# ESP32_RelayBoard.net
KiCad netlist of a schematic drawn in EasyEDA Pro
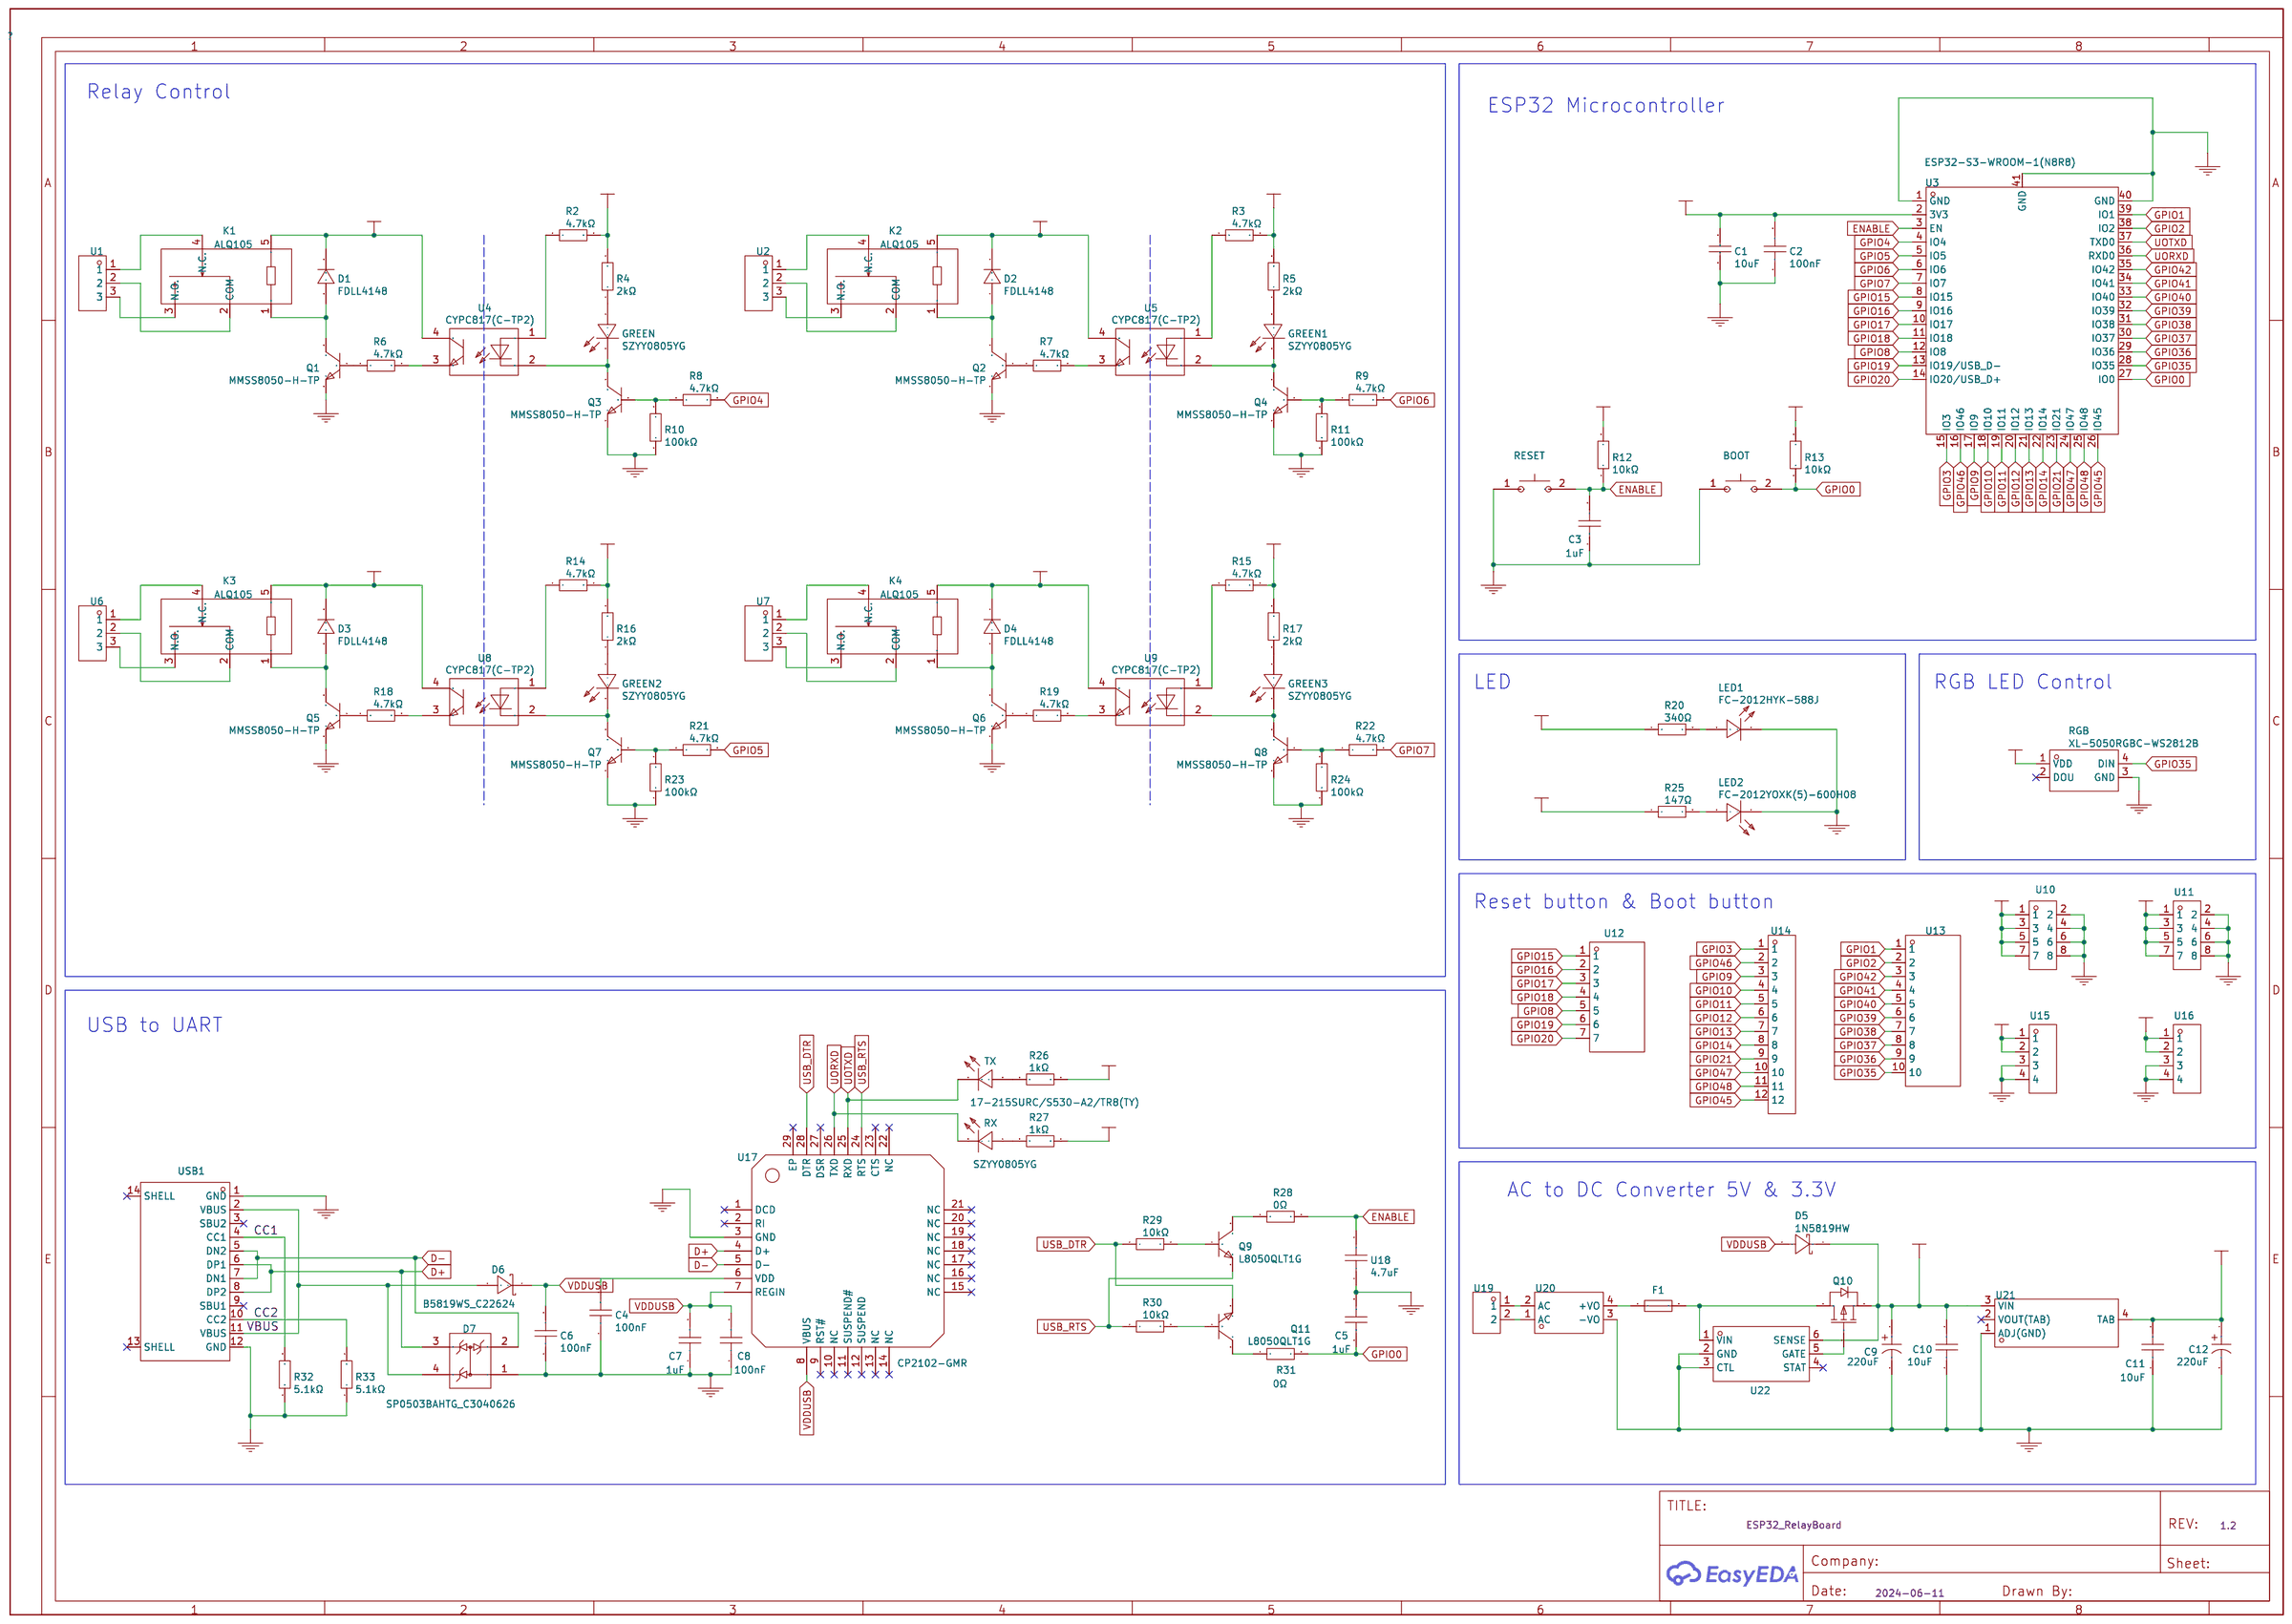
[diagram p0: schematic sheet]

(export (version "E")
  (design (tool "Eeschema 10.0.6"))
  (components
    (comp (ref "BOOT")
      (value "TS-1101S-C-B-B-B-A")
      (footprint "easyedapro:SW-SMD_L6.0-W3.5-LS8.0")
      (fields (field (name "Manufacturer") "XKB Connectivity(中国星坤)"))
      (libsource (lib "easyedapro") (part "TS-1101S-C-B-B-B-A"))
    )
    (comp (ref "C1")
      (value "10uF")
      (footprint "easyedapro:C0402")
      (fields
        (field (name "Manufacturer Part") "CC0402MRX5R5BB106")
        (field (name "Manufacturer") "YAGEO(国巨)")
      )
      (libsource (lib "") (part "10uF_1"))
    )
    (comp (ref "C2")
      (value "100nF")
      (footprint "easyedapro:C0402")
      (fields
        (field (name "Manufacturer Part") "CSA0402X7R104K250GT")
        (field (name "Manufacturer") "HRE(芯声)")
      )
      (libsource (lib "easyedapro") (part "100nF"))
    )
    (comp (ref "C3")
      (value "1uF")
      (footprint "easyedapro:C0402")
      (fields
        (field (name "Manufacturer Part") "HGC0402R5105K500NTEJ")
        (field (name "Manufacturer") "Chinocera(华瓷)")
      )
      (libsource (lib "easyedapro") (part "1uF"))
    )
    (comp (ref "C4")
      (value "100nF")
      (footprint "easyedapro:C0402")
      (fields
        (field (name "Manufacturer Part") "CSA0402X7R104K250GT")
        (field (name "Manufacturer") "HRE(芯声)")
      )
      (libsource (lib "easyedapro") (part "100nF"))
    )
    (comp (ref "C5")
      (value "1uF")
      (footprint "easyedapro:C0402")
      (fields
        (field (name "Manufacturer Part") "HGC0402R5105K500NTEJ")
        (field (name "Manufacturer") "Chinocera(华瓷)")
      )
      (libsource (lib "easyedapro") (part "1uF"))
    )
    (comp (ref "C6")
      (value "100nF")
      (footprint "easyedapro:C0402")
      (fields
        (field (name "Manufacturer Part") "CSA0402X7R104K250GT")
        (field (name "Manufacturer") "HRE(芯声)")
      )
      (libsource (lib "easyedapro") (part "100nF"))
    )
    (comp (ref "C7")
      (value "1uF")
      (footprint "easyedapro:C0402")
      (fields
        (field (name "Manufacturer Part") "HGC0402R5105K500NTEJ")
        (field (name "Manufacturer") "Chinocera(华瓷)")
      )
      (libsource (lib "easyedapro") (part "1uF"))
    )
    (comp (ref "C8")
      (value "100nF")
      (footprint "easyedapro:C0402")
      (fields
        (field (name "Manufacturer Part") "CSA0402X7R104K250GT")
        (field (name "Manufacturer") "HRE(芯声)")
      )
      (libsource (lib "easyedapro") (part "100nF"))
    )
    (comp (ref "C9")
      (value "220uF")
      (footprint "easyedapro:CAP-SMD_BD6.3-L6.6-W6.6-LS7.2-FD")
      (fields
        (field (name "Manufacturer Part") "MVG 16V 220UF 6.3*7.7")
        (field (name "Manufacturer") "SAMYOUNG(韩国三莹)")
      )
      (libsource (lib "easyedapro") (part "220uF"))
    )
    (comp (ref "C10")
      (value "10uF")
      (footprint "easyedapro:C0805")
      (fields (field (name "Manufacturer Part") "0805F106M160NT") (field (name "Manufacturer") "FH(风华)"))
      (libsource (lib "easyedapro") (part "10uF"))
    )
    (comp (ref "C11")
      (value "10uF")
      (footprint "easyedapro:C0805")
      (fields (field (name "Manufacturer Part") "0805F106M160NT") (field (name "Manufacturer") "FH(风华)"))
      (libsource (lib "easyedapro") (part "10uF"))
    )
    (comp (ref "C12")
      (value "220uF")
      (footprint "easyedapro:CAP-SMD_BD6.3-L6.6-W6.6-LS7.2-FD")
      (fields
        (field (name "Manufacturer Part") "MVG 16V 220UF 6.3*7.7")
        (field (name "Manufacturer") "SAMYOUNG(韩国三莹)")
      )
      (libsource (lib "easyedapro") (part "220uF"))
    )
    (comp (ref "D1")
      (value "FDLL4148")
      (footprint "easyedapro:SOD-80_L3.5-W1.5-RD")
      (fields (field (name "Manufacturer") "onsemi(安森美)"))
      (libsource (lib "easyedapro") (part "FDLL4148"))
    )
    (comp (ref "D2")
      (value "FDLL4148")
      (footprint "easyedapro:SOD-80_L3.5-W1.5-RD")
      (fields (field (name "Manufacturer") "onsemi(安森美)"))
      (libsource (lib "easyedapro") (part "FDLL4148"))
    )
    (comp (ref "D3")
      (value "FDLL4148")
      (footprint "easyedapro:SOD-80_L3.5-W1.5-RD")
      (fields (field (name "Manufacturer") "onsemi(安森美)"))
      (libsource (lib "easyedapro") (part "FDLL4148"))
    )
    (comp (ref "D4")
      (value "FDLL4148")
      (footprint "easyedapro:SOD-80_L3.5-W1.5-RD")
      (fields (field (name "Manufacturer") "onsemi(安森美)"))
      (libsource (lib "easyedapro") (part "FDLL4148"))
    )
    (comp (ref "D5")
      (value "1N5819HW")
      (footprint "easyedapro:SOD-123_L2.7-W1.6-LS3.7-RD-1")
      (fields (field (name "Manufacturer") "TECH PUBLIC(台舟)"))
      (libsource (lib "easyedapro") (part "1N5819HW"))
    )
    (comp (ref "D6")
      (value "B5819WS_C22624")
      (footprint "easyedapro:SOD-323_L1.8-W1.3-LS2.5-RD")
      (fields (field (name "Manufacturer Part") "B5819WS") (field (name "Manufacturer") "CJ(江苏长电/长晶)"))
      (libsource (lib "easyedapro") (part "B5819WS_C22624"))
    )
    (comp (ref "D7")
      (value "SP0503BAHTG_C3040626")
      (footprint "easyedapro:SOT-143-4_L2.9-W1.3-P1.92-LS2.4-BL")
      (fields
        (field (name "Manufacturer Part") "SP0503BAHTG")
        (field (name "Manufacturer") "TECH PUBLIC(台舟)")
      )
      (libsource (lib "easyedapro") (part "SP0503BAHTG_C3040626"))
    )
    (comp (ref "F1")
      (value "BSMD0805-100-6V")
      (footprint "easyedapro:F0805")
      (fields (field (name "Manufacturer") "BHFUSE(佰宏)"))
      (libsource (lib "easyedapro") (part "BSMD0805-100-6V"))
    )
    (comp (ref "GREEN")
      (value "SZYY0805YG")
      (footprint "easyedapro:LED0805-R-RD_GREEN")
      (fields (field (name "Manufacturer") "yongyu(永裕光电)"))
      (libsource (lib "easyedapro") (part "SZYY0805YG"))
    )
    (comp (ref "GREEN1")
      (value "SZYY0805YG")
      (footprint "easyedapro:LED0805-R-RD_GREEN")
      (fields (field (name "Manufacturer") "yongyu(永裕光电)"))
      (libsource (lib "easyedapro") (part "SZYY0805YG"))
    )
    (comp (ref "GREEN2")
      (value "SZYY0805YG")
      (footprint "easyedapro:LED0805-R-RD_GREEN")
      (fields (field (name "Manufacturer") "yongyu(永裕光电)"))
      (libsource (lib "easyedapro") (part "SZYY0805YG"))
    )
    (comp (ref "GREEN3")
      (value "SZYY0805YG")
      (footprint "easyedapro:LED0805-R-RD_GREEN")
      (fields (field (name "Manufacturer") "yongyu(永裕光电)"))
      (libsource (lib "easyedapro") (part "SZYY0805YG"))
    )
    (comp (ref "K1")
      (value "ALQ105")
      (footprint "easyedapro:RELAY-TH_ALQ1XX")
      (fields (field (name "Manufacturer") "PANASONIC(松下)"))
      (libsource (lib "easyedapro") (part "ALQ105"))
    )
    (comp (ref "K2")
      (value "ALQ105")
      (footprint "easyedapro:RELAY-TH_ALQ1XX")
      (fields (field (name "Manufacturer") "PANASONIC(松下)"))
      (libsource (lib "easyedapro") (part "ALQ105"))
    )
    (comp (ref "K3")
      (value "ALQ105")
      (footprint "easyedapro:RELAY-TH_ALQ1XX")
      (fields (field (name "Manufacturer") "PANASONIC(松下)"))
      (libsource (lib "easyedapro") (part "ALQ105"))
    )
    (comp (ref "K4")
      (value "ALQ105")
      (footprint "easyedapro:RELAY-TH_ALQ1XX")
      (fields (field (name "Manufacturer") "PANASONIC(松下)"))
      (libsource (lib "easyedapro") (part "ALQ105"))
    )
    (comp (ref "LED1")
      (value "FC-2012HYK-588J")
      (footprint "easyedapro:LED0805-R-RD")
      (fields (field (name "Manufacturer Part") "NCD0805Y1") (field (name "Manufacturer") "国星光电"))
      (libsource (lib "easyedapro") (part "FC-2012HYK-588J"))
    )
    (comp (ref "LED2")
      (value "FC-2012YOXK(5)-600H08")
      (footprint "easyedapro:LED0805-RD_ORANGE")
      (fields (field (name "Manufacturer Part") "NCD0805O1") (field (name "Manufacturer") "国星光电"))
      (libsource (lib "easyedapro") (part "FC-2012YOXK(5)-600H08"))
    )
    (comp (ref "Q1")
      (value "MMSS8050-H-TP")
      (footprint "easyedapro:SOT-23-3_L2.9-W1.6-P1.90-LS2.8-BR")
      (fields (field (name "Manufacturer") "MCC(美微科)"))
      (libsource (lib "easyedapro") (part "MMSS8050-H-TP"))
    )
    (comp (ref "Q2")
      (value "MMSS8050-H-TP")
      (footprint "easyedapro:SOT-23-3_L2.9-W1.6-P1.90-LS2.8-BR")
      (fields (field (name "Manufacturer") "MCC(美微科)"))
      (libsource (lib "easyedapro") (part "MMSS8050-H-TP"))
    )
    (comp (ref "Q3")
      (value "MMSS8050-H-TP")
      (footprint "easyedapro:SOT-23-3_L2.9-W1.6-P1.90-LS2.8-BR")
      (fields (field (name "Manufacturer") "MCC(美微科)"))
      (libsource (lib "easyedapro") (part "MMSS8050-H-TP"))
    )
    (comp (ref "Q4")
      (value "MMSS8050-H-TP")
      (footprint "easyedapro:SOT-23-3_L2.9-W1.6-P1.90-LS2.8-BR")
      (fields (field (name "Manufacturer") "MCC(美微科)"))
      (libsource (lib "easyedapro") (part "MMSS8050-H-TP"))
    )
    (comp (ref "Q5")
      (value "MMSS8050-H-TP")
      (footprint "easyedapro:SOT-23-3_L2.9-W1.6-P1.90-LS2.8-BR")
      (fields (field (name "Manufacturer") "MCC(美微科)"))
      (libsource (lib "easyedapro") (part "MMSS8050-H-TP"))
    )
    (comp (ref "Q6")
      (value "MMSS8050-H-TP")
      (footprint "easyedapro:SOT-23-3_L2.9-W1.6-P1.90-LS2.8-BR")
      (fields (field (name "Manufacturer") "MCC(美微科)"))
      (libsource (lib "easyedapro") (part "MMSS8050-H-TP"))
    )
    (comp (ref "Q7")
      (value "MMSS8050-H-TP")
      (footprint "easyedapro:SOT-23-3_L2.9-W1.6-P1.90-LS2.8-BR")
      (fields (field (name "Manufacturer") "MCC(美微科)"))
      (libsource (lib "easyedapro") (part "MMSS8050-H-TP"))
    )
    (comp (ref "Q8")
      (value "MMSS8050-H-TP")
      (footprint "easyedapro:SOT-23-3_L2.9-W1.6-P1.90-LS2.8-BR")
      (fields (field (name "Manufacturer") "MCC(美微科)"))
      (libsource (lib "easyedapro") (part "MMSS8050-H-TP"))
    )
    (comp (ref "Q9")
      (value "L8050QLT1G")
      (footprint "easyedapro:SOT-23-3_L2.9-W1.3-P1.90-LS2.4-BR")
      (fields (field (name "Manufacturer") "LRC(乐山无线电)"))
      (libsource (lib "") (part "L8050QLT1G_1"))
    )
    (comp (ref "Q10")
      (value "FDN306P")
      (footprint "easyedapro:SOT-23-3_L3.0-W1.7-P0.95-LS2.9-BR")
      (fields (field (name "Manufacturer") "onsemi(安森美)"))
      (libsource (lib "easyedapro") (part "FDN306P"))
    )
    (comp (ref "Q11")
      (value "L8050QLT1G")
      (footprint "easyedapro:SOT-23-3_L2.9-W1.3-P1.90-LS2.4-BR")
      (fields (field (name "Manufacturer") "LRC(乐山无线电)"))
      (libsource (lib "easyedapro") (part "L8050QLT1G"))
    )
    (comp (ref "R2")
      (value "4.7kΩ")
      (footprint "easyedapro:R0805")
      (fields
        (field (name "Manufacturer Part") "0805W8F4701T5E")
        (field (name "Manufacturer") "UNI-ROYAL(厚声)")
      )
      (libsource (lib "easyedapro") (part "4.7kΩ"))
    )
    (comp (ref "R3")
      (value "4.7kΩ")
      (footprint "easyedapro:R0805")
      (fields
        (field (name "Manufacturer Part") "0805W8F4701T5E")
        (field (name "Manufacturer") "UNI-ROYAL(厚声)")
      )
      (libsource (lib "easyedapro") (part "4.7kΩ"))
    )
    (comp (ref "R4")
      (value "2kΩ")
      (footprint "easyedapro:R0805")
      (fields
        (field (name "Manufacturer Part") "0805W8F2001T5E")
        (field (name "Manufacturer") "UNI-ROYAL(厚声)")
      )
      (libsource (lib "easyedapro") (part "2kΩ"))
    )
    (comp (ref "R5")
      (value "2kΩ")
      (footprint "easyedapro:R0805")
      (fields
        (field (name "Manufacturer Part") "0805W8F2001T5E")
        (field (name "Manufacturer") "UNI-ROYAL(厚声)")
      )
      (libsource (lib "easyedapro") (part "2kΩ"))
    )
    (comp (ref "R6")
      (value "4.7kΩ")
      (footprint "easyedapro:R0805")
      (fields
        (field (name "Manufacturer Part") "0805W8F4701T5E")
        (field (name "Manufacturer") "UNI-ROYAL(厚声)")
      )
      (libsource (lib "easyedapro") (part "4.7kΩ"))
    )
    (comp (ref "R7")
      (value "4.7kΩ")
      (footprint "easyedapro:R0805")
      (fields
        (field (name "Manufacturer Part") "0805W8F4701T5E")
        (field (name "Manufacturer") "UNI-ROYAL(厚声)")
      )
      (libsource (lib "easyedapro") (part "4.7kΩ"))
    )
    (comp (ref "R8")
      (value "4.7kΩ")
      (footprint "easyedapro:R0805")
      (fields
        (field (name "Manufacturer Part") "0805W8F4701T5E")
        (field (name "Manufacturer") "UNI-ROYAL(厚声)")
      )
      (libsource (lib "easyedapro") (part "4.7kΩ"))
    )
    (comp (ref "R9")
      (value "4.7kΩ")
      (footprint "easyedapro:R0805")
      (fields
        (field (name "Manufacturer Part") "0805W8F4701T5E")
        (field (name "Manufacturer") "UNI-ROYAL(厚声)")
      )
      (libsource (lib "easyedapro") (part "4.7kΩ"))
    )
    (comp (ref "R10")
      (value "100kΩ")
      (footprint "easyedapro:R0805")
      (fields
        (field (name "Manufacturer Part") "0805W8F1003T5E")
        (field (name "Manufacturer") "UNI-ROYAL(厚声)")
      )
      (libsource (lib "easyedapro") (part "100kΩ"))
    )
    (comp (ref "R11")
      (value "100kΩ")
      (footprint "easyedapro:R0805")
      (fields
        (field (name "Manufacturer Part") "0805W8F1003T5E")
        (field (name "Manufacturer") "UNI-ROYAL(厚声)")
      )
      (libsource (lib "easyedapro") (part "100kΩ"))
    )
    (comp (ref "R12")
      (value "10kΩ")
      (footprint "easyedapro:R0402")
      (fields (field (name "Manufacturer Part") "RT0402DRE0710KL") (field (name "Manufacturer") "YAGEO(国巨)"))
      (libsource (lib "easyedapro") (part "10kΩ"))
    )
    (comp (ref "R13")
      (value "10kΩ")
      (footprint "easyedapro:R0402")
      (fields (field (name "Manufacturer Part") "RT0402DRE0710KL") (field (name "Manufacturer") "YAGEO(国巨)"))
      (libsource (lib "easyedapro") (part "10kΩ"))
    )
    (comp (ref "R14")
      (value "4.7kΩ")
      (footprint "easyedapro:R0805")
      (fields
        (field (name "Manufacturer Part") "0805W8F4701T5E")
        (field (name "Manufacturer") "UNI-ROYAL(厚声)")
      )
      (libsource (lib "easyedapro") (part "4.7kΩ"))
    )
    (comp (ref "R15")
      (value "4.7kΩ")
      (footprint "easyedapro:R0805")
      (fields
        (field (name "Manufacturer Part") "0805W8F4701T5E")
        (field (name "Manufacturer") "UNI-ROYAL(厚声)")
      )
      (libsource (lib "easyedapro") (part "4.7kΩ"))
    )
    (comp (ref "R16")
      (value "2kΩ")
      (footprint "easyedapro:R0805")
      (fields
        (field (name "Manufacturer Part") "0805W8F2001T5E")
        (field (name "Manufacturer") "UNI-ROYAL(厚声)")
      )
      (libsource (lib "easyedapro") (part "2kΩ"))
    )
    (comp (ref "R17")
      (value "2kΩ")
      (footprint "easyedapro:R0805")
      (fields
        (field (name "Manufacturer Part") "0805W8F2001T5E")
        (field (name "Manufacturer") "UNI-ROYAL(厚声)")
      )
      (libsource (lib "easyedapro") (part "2kΩ"))
    )
    (comp (ref "R18")
      (value "4.7kΩ")
      (footprint "easyedapro:R0805")
      (fields
        (field (name "Manufacturer Part") "0805W8F4701T5E")
        (field (name "Manufacturer") "UNI-ROYAL(厚声)")
      )
      (libsource (lib "easyedapro") (part "4.7kΩ"))
    )
    (comp (ref "R19")
      (value "4.7kΩ")
      (footprint "easyedapro:R0805")
      (fields
        (field (name "Manufacturer Part") "0805W8F4701T5E")
        (field (name "Manufacturer") "UNI-ROYAL(厚声)")
      )
      (libsource (lib "easyedapro") (part "4.7kΩ"))
    )
    (comp (ref "R20")
      (value "340Ω")
      (footprint "easyedapro:R0805")
      (fields (field (name "Manufacturer Part") "CR0805F83400G") (field (name "Manufacturer") "LIZ(丽智电子)"))
      (libsource (lib "easyedapro") (part "340Ω"))
    )
    (comp (ref "R21")
      (value "4.7kΩ")
      (footprint "easyedapro:R0805")
      (fields
        (field (name "Manufacturer Part") "0805W8F4701T5E")
        (field (name "Manufacturer") "UNI-ROYAL(厚声)")
      )
      (libsource (lib "easyedapro") (part "4.7kΩ"))
    )
    (comp (ref "R22")
      (value "4.7kΩ")
      (footprint "easyedapro:R0805")
      (fields
        (field (name "Manufacturer Part") "0805W8F4701T5E")
        (field (name "Manufacturer") "UNI-ROYAL(厚声)")
      )
      (libsource (lib "easyedapro") (part "4.7kΩ"))
    )
    (comp (ref "R23")
      (value "100kΩ")
      (footprint "easyedapro:R0805")
      (fields
        (field (name "Manufacturer Part") "0805W8F1003T5E")
        (field (name "Manufacturer") "UNI-ROYAL(厚声)")
      )
      (libsource (lib "easyedapro") (part "100kΩ"))
    )
    (comp (ref "R24")
      (value "100kΩ")
      (footprint "easyedapro:R0805")
      (fields
        (field (name "Manufacturer Part") "0805W8F1003T5E")
        (field (name "Manufacturer") "UNI-ROYAL(厚声)")
      )
      (libsource (lib "easyedapro") (part "100kΩ"))
    )
    (comp (ref "R25")
      (value "147Ω")
      (footprint "easyedapro:R0805")
      (fields (field (name "Manufacturer Part") "CR0805-FX-1470ELF") (field (name "Manufacturer") "BOURNS"))
      (libsource (lib "easyedapro") (part "147Ω"))
    )
    (comp (ref "R26")
      (value "1kΩ")
      (footprint "easyedapro:R0805")
      (fields (field (name "Manufacturer Part") "RMC08051K5%N") (field (name "Manufacturer") "Tyohm(幸亚电阻)"))
      (libsource (lib "easyedapro") (part "1kΩ"))
    )
    (comp (ref "R27")
      (value "1kΩ")
      (footprint "easyedapro:R0805")
      (fields (field (name "Manufacturer Part") "RMC08051K5%N") (field (name "Manufacturer") "Tyohm(幸亚电阻)"))
      (libsource (lib "easyedapro") (part "1kΩ"))
    )
    (comp (ref "R28")
      (value "0Ω")
      (footprint "easyedapro:R0402")
      (fields (field (name "Manufacturer Part") "RC0402FR-070RL") (field (name "Manufacturer") "YAGEO(国巨)"))
      (libsource (lib "easyedapro") (part "0Ω"))
    )
    (comp (ref "R29")
      (value "10kΩ")
      (footprint "easyedapro:R0402")
      (fields (field (name "Manufacturer Part") "RT0402DRE0710KL") (field (name "Manufacturer") "YAGEO(国巨)"))
      (libsource (lib "easyedapro") (part "10kΩ"))
    )
    (comp (ref "R30")
      (value "10kΩ")
      (footprint "easyedapro:R0402")
      (fields (field (name "Manufacturer Part") "RT0402DRE0710KL") (field (name "Manufacturer") "YAGEO(国巨)"))
      (libsource (lib "easyedapro") (part "10kΩ"))
    )
    (comp (ref "R31")
      (value "0Ω")
      (footprint "easyedapro:R0402")
      (fields (field (name "Manufacturer Part") "RC0402FR-070RL") (field (name "Manufacturer") "YAGEO(国巨)"))
      (libsource (lib "easyedapro") (part "0Ω"))
    )
    (comp (ref "R32")
      (value "5.1kΩ")
      (footprint "easyedapro:R0402")
      (fields (field (name "Manufacturer Part") "RMC04025.1K1%N") (field (name "Manufacturer") "Tyohm(幸亚电阻)"))
      (libsource (lib "easyedapro") (part "5.1kΩ"))
    )
    (comp (ref "R33")
      (value "5.1kΩ")
      (footprint "easyedapro:R0402")
      (fields (field (name "Manufacturer Part") "RMC04025.1K1%N") (field (name "Manufacturer") "Tyohm(幸亚电阻)"))
      (libsource (lib "easyedapro") (part "5.1kΩ"))
    )
    (comp (ref "RESET")
      (value "TS-1101S-C-B-B-B-A")
      (footprint "easyedapro:SW-SMD_L6.0-W3.5-LS8.0")
      (fields (field (name "Manufacturer") "XKB Connectivity(中国星坤)"))
      (libsource (lib "easyedapro") (part "TS-1101S-C-B-B-B-A"))
    )
    (comp (ref "RGB")
      (value "XL-5050RGBC-WS2812B")
      (footprint "easyedapro:LED-SMD_4P-L5.0-W5.0-BL_XL-5050RGBC")
      (fields (field (name "Manufacturer") "XINGLIGHT(成兴光)"))
      (libsource (lib "easyedapro") (part "XL-5050RGBC-WS2812B"))
    )
    (comp (ref "RX")
      (value "SZYY0805YG")
      (footprint "easyedapro:LED0805-R-RD_GREEN")
      (fields (field (name "Manufacturer") "yongyu(永裕光电)"))
      (libsource (lib "easyedapro") (part "SZYY0805YG"))
    )
    (comp (ref "TX")
      (value "17-215SURC/S530-A2/TR8(TY)")
      (footprint "easyedapro:LED0805-RD_RED")
      (fields
        (field (name "Manufacturer Part") "17-215SURC/S530-A2/TR8")
        (field (name "Manufacturer") "EVERLIGHT(亿光)")
      )
      (libsource (lib "easyedapro") (part "17-215SURC/S530-A2/TR8(TY)"))
    )
    (comp (ref "U1")
      (value "DB128L-5.08-3P-BK-S")
      (footprint "easyedapro:CONN-TH_3P-P5.08_DB128L-5.08-3P-BK-S")
      (fields (field (name "Manufacturer") "DORABO(地博电气)"))
      (libsource (lib "easyedapro") (part "DB128L-5.08-3P-BK-S"))
    )
    (comp (ref "U2")
      (value "DB128L-5.08-3P-BK-S")
      (footprint "easyedapro:CONN-TH_3P-P5.08_DB128L-5.08-3P-BK-S")
      (fields (field (name "Manufacturer") "DORABO(地博电气)"))
      (libsource (lib "easyedapro") (part "DB128L-5.08-3P-BK-S"))
    )
    (comp (ref "U3")
      (value "ESP32-S3-WROOM-1(N8R8)")
      (footprint "easyedapro:WIRELM-SMD_ESP32-S3-WROOM-1")
      (fields
        (field (name "Manufacturer Part") "ESP32-S3-WROOM-1-N8R8")
        (field (name "Manufacturer") "ESPRESSIF(乐鑫)")
      )
      (libsource (lib "easyedapro") (part "ESP32-S3-WROOM-1(N8R8)"))
    )
    (comp (ref "U4")
      (value "CYPC817(C-TP2)")
      (footprint "easyedapro:SOP-4_L6.4-W4.6-P2.54-LS10.2-TL")
      (fields (field (name "Manufacturer") "OCIC(卓睿科)"))
      (libsource (lib "easyedapro") (part "CYPC817(C-TP2)"))
    )
    (comp (ref "U5")
      (value "CYPC817(C-TP2)")
      (footprint "easyedapro:SOP-4_L6.4-W4.6-P2.54-LS10.2-TL")
      (fields (field (name "Manufacturer") "OCIC(卓睿科)"))
      (libsource (lib "easyedapro") (part "CYPC817(C-TP2)"))
    )
    (comp (ref "U6")
      (value "DB128L-5.08-3P-BK-S")
      (footprint "easyedapro:CONN-TH_3P-P5.08_DB128L-5.08-3P-BK-S")
      (fields (field (name "Manufacturer") "DORABO(地博电气)"))
      (libsource (lib "easyedapro") (part "DB128L-5.08-3P-BK-S"))
    )
    (comp (ref "U7")
      (value "DB128L-5.08-3P-BK-S")
      (footprint "easyedapro:CONN-TH_3P-P5.08_DB128L-5.08-3P-BK-S")
      (fields (field (name "Manufacturer") "DORABO(地博电气)"))
      (libsource (lib "easyedapro") (part "DB128L-5.08-3P-BK-S"))
    )
    (comp (ref "U8")
      (value "CYPC817(C-TP2)")
      (footprint "easyedapro:SOP-4_L6.4-W4.6-P2.54-LS10.2-TL")
      (fields (field (name "Manufacturer") "OCIC(卓睿科)"))
      (libsource (lib "easyedapro") (part "CYPC817(C-TP2)"))
    )
    (comp (ref "U9")
      (value "CYPC817(C-TP2)")
      (footprint "easyedapro:SOP-4_L6.4-W4.6-P2.54-LS10.2-TL")
      (fields (field (name "Manufacturer") "OCIC(卓睿科)"))
      (libsource (lib "easyedapro") (part "CYPC817(C-TP2)"))
    )
    (comp (ref "U10")
      (value "ZX-PM2.54-2-4PY")
      (footprint "easyedapro:HDR-TH_8P-P2.54-V-F-R2-C4-S2.54")
      (fields (field (name "Manufacturer") "Megastar(兆星)"))
      (libsource (lib "easyedapro") (part "ZX-PM2.54-2-4PY"))
    )
    (comp (ref "U11")
      (value "ZX-PM2.54-2-4PY")
      (footprint "easyedapro:HDR-TH_8P-P2.54-V-F-R2-C4-S2.54")
      (fields (field (name "Manufacturer") "Megastar(兆星)"))
      (libsource (lib "easyedapro") (part "ZX-PM2.54-2-4PY"))
    )
    (comp (ref "U12")
      (value "A2541HWV-7P")
      (footprint "easyedapro:HDR-TH_7P-P2.54-V_A2541HWV-7P")
      (fields (field (name "Manufacturer") "CJT(长江连接器)"))
      (libsource (lib "easyedapro") (part "A2541HWV-7P"))
    )
    (comp (ref "U13")
      (value "A2541HWV-10P")
      (footprint "easyedapro:HDR-TH_10P-P2.54-V-F-1")
      (fields (field (name "Manufacturer") "CJT(长江连接器)"))
      (libsource (lib "easyedapro") (part "A2541HWV-10P"))
    )
    (comp (ref "U14")
      (value "ZX-PM2.54-1-12PY")
      (footprint "easyedapro:HDR-TH_12P-P2.54-V-F")
      (fields (field (name "Manufacturer") "Megastar(兆星)"))
      (libsource (lib "easyedapro") (part "ZX-PM2.54-1-12PY"))
    )
    (comp (ref "U15")
      (value "HB-PH3-25414PB2GOP")
      (footprint "easyedapro:HDR-TH_4P-P2.54-V-M")
      (fields (field (name "Manufacturer") "HANBO(汉博)"))
      (libsource (lib "easyedapro") (part "HB-PH3-25414PB2GOP"))
    )
    (comp (ref "U16")
      (value "HB-PH3-25414PB2GOP")
      (footprint "easyedapro:HDR-TH_4P-P2.54-V-M")
      (fields (field (name "Manufacturer") "HANBO(汉博)"))
      (libsource (lib "easyedapro") (part "HB-PH3-25414PB2GOP"))
    )
    (comp (ref "U17")
      (value "CP2102-GMR")
      (footprint "easyedapro:WQFN-28_L5.0-W5.0-P0.50-BL-EP3.2")
      (fields (field (name "Manufacturer") "SKYWORKS/SILICON LABS(芯科)"))
      (libsource (lib "easyedapro") (part "CP2102-GMR"))
    )
    (comp (ref "U18")
      (value "4.7uF")
      (footprint "easyedapro:C0402")
      (fields
        (field (name "Manufacturer Part") "HGC0402R5475K100NTEJ")
        (field (name "Manufacturer") "Chinocera(华瓷)")
      )
      (libsource (lib "easyedapro") (part "4.7uF"))
    )
    (comp (ref "U19")
      (value "DB128L-5.08-2P-BK-S")
      (footprint "easyedapro:CONN-TH_2P-P5.08_DB128L-5.08-2P-BK-S")
      (fields (field (name "Manufacturer") "DORABO(地博电气)"))
      (libsource (lib "easyedapro") (part "DB128L-5.08-2P-BK-S"))
    )
    (comp (ref "U20")
      (value "HLK-10M05")
      (footprint "easyedapro:PWRM-TH_HLK-10M05")
      (fields (field (name "Manufacturer") "HI-LINK(海凌科)"))
      (libsource (lib "easyedapro") (part "HLK-10M05"))
    )
    (comp (ref "U21")
      (value "AMS1117-3.3_C347222")
      (footprint "easyedapro:SOT-223-4_L6.5-W3.5-P2.30-LS7.0-BR")
      (fields (field (name "Manufacturer Part") "AMS1117-3.3") (field (name "Manufacturer") "UMW(友台半导体)"))
      (libsource (lib "easyedapro") (part "AMS1117-3.3_C347222"))
    )
    (comp (ref "U22")
      (value "LTC4412HVIS6#TRPBF")
      (footprint "easyedapro:TSOT-23-6_L2.9-W1.6-P0.95-LS2.8-BR")
      (fields (field (name "Manufacturer") "ADI(亚德诺)"))
      (libsource (lib "easyedapro") (part "LTC4412HVIS6#TRPBF"))
    )
    (comp (ref "USB1")
      (value "TYPE-C 16PIN 2MD(073)")
      (footprint "easyedapro:USB-C-SMD_TYPE-C-6PIN-2MD-073")
      (fields (field (name "Manufacturer") "SHOU HAN(首韩)"))
      (libsource (lib "easyedapro") (part "TYPE-C 16PIN 2MD(073)"))
    )
  )
  (nets
    (net (code "1") (name "+5V") (class "Default")
      (node (ref "C10") (pin "2") (pinfunction "2_2") (pintype "unspecified"))
      (node (ref "C9") (pin "1") (pinfunction "1_1") (pintype "input"))
      (node (ref "D1") (pin "1") (pinfunction "C_1") (pintype "unspecified"))
      (node (ref "D2") (pin "1") (pinfunction "C_1") (pintype "unspecified"))
      (node (ref "D3") (pin "1") (pinfunction "C_1") (pintype "unspecified"))
      (node (ref "D4") (pin "1") (pinfunction "C_1") (pintype "unspecified"))
      (node (ref "D5") (pin "1") (pinfunction "K_1") (pintype "unspecified"))
      (node (ref "K1") (pin "5") (pinfunction "5_5") (pintype "unspecified"))
      (node (ref "K2") (pin "5") (pinfunction "5_5") (pintype "unspecified"))
      (node (ref "K3") (pin "5") (pinfunction "5_5") (pintype "unspecified"))
      (node (ref "K4") (pin "5") (pinfunction "5_5") (pintype "unspecified"))
      (node (ref "Q10") (pin "2") (pinfunction "S_2") (pintype "unspecified"))
      (node (ref "R20") (pin "1") (pinfunction "1_1") (pintype "unspecified"))
      (node (ref "RGB") (pin "1") (pinfunction "VDD_1") (pintype "unspecified"))
      (node (ref "U11") (pin "1") (pinfunction "1_1") (pintype "unspecified"))
      (node (ref "U11") (pin "3") (pinfunction "3_3") (pintype "unspecified"))
      (node (ref "U11") (pin "5") (pinfunction "5_5") (pintype "unspecified"))
      (node (ref "U11") (pin "7") (pinfunction "7_7") (pintype "unspecified"))
      (node (ref "U16") (pin "1") (pinfunction "1_1") (pintype "unspecified"))
      (node (ref "U16") (pin "2") (pinfunction "2_2") (pintype "unspecified"))
      (node (ref "U21") (pin "3") (pinfunction "VIN_3") (pintype "unspecified"))
      (node (ref "U22") (pin "6") (pinfunction "SENSE_6") (pintype "unspecified"))
      (node (ref "U4") (pin "4") (pinfunction "COL_4") (pintype "unspecified"))
      (node (ref "U5") (pin "4") (pinfunction "COL_4") (pintype "unspecified"))
      (node (ref "U8") (pin "4") (pinfunction "COL_4") (pintype "unspecified"))
      (node (ref "U9") (pin "4") (pinfunction "COL_4") (pintype "unspecified"))
    )
    (net (code "2") (name "/CC1") (class "Default")
      (node (ref "R32") (pin "2") (pinfunction "2_2") (pintype "unspecified"))
      (node (ref "USB1") (pin "4") (pinfunction "CC1_4") (pintype "unspecified"))
    )
    (net (code "3") (name "/CC2") (class "Default")
      (node (ref "R33") (pin "2") (pinfunction "2_2") (pintype "unspecified"))
      (node (ref "USB1") (pin "10") (pinfunction "CC2_10") (pintype "unspecified"))
    )
    (net (code "4") (name "/VBUS") (class "Default")
      (node (ref "D6") (pin "2") (pinfunction "A_2") (pintype "unspecified"))
      (node (ref "D7") (pin "4") (pinfunction "4_4") (pintype "input"))
      (node (ref "USB1") (pin "11") (pinfunction "VBUS_11") (pintype "unspecified"))
      (node (ref "USB1") (pin "2") (pinfunction "VBUS_2") (pintype "unspecified"))
    )
    (net (code "5") (name "3V3") (class "Default")
      (node (ref "C1") (pin "2") (pinfunction "2_2") (pintype "input"))
      (node (ref "C11") (pin "2") (pinfunction "2_2") (pintype "unspecified"))
      (node (ref "C12") (pin "1") (pinfunction "1_1") (pintype "input"))
      (node (ref "C2") (pin "2") (pinfunction "2_2") (pintype "unspecified"))
      (node (ref "R12") (pin "2") (pinfunction "2_2") (pintype "unspecified"))
      (node (ref "R13") (pin "2") (pinfunction "2_2") (pintype "unspecified"))
      (node (ref "R14") (pin "2") (pinfunction "2_2") (pintype "input"))
      (node (ref "R15") (pin "2") (pinfunction "2_2") (pintype "input"))
      (node (ref "R16") (pin "2") (pinfunction "2_2") (pintype "input"))
      (node (ref "R17") (pin "2") (pinfunction "2_2") (pintype "input"))
      (node (ref "R2") (pin "2") (pinfunction "2_2") (pintype "input"))
      (node (ref "R25") (pin "1") (pinfunction "1_1") (pintype "unspecified"))
      (node (ref "R26") (pin "1") (pinfunction "1_1") (pintype "unspecified"))
      (node (ref "R27") (pin "1") (pinfunction "1_1") (pintype "unspecified"))
      (node (ref "R3") (pin "2") (pinfunction "2_2") (pintype "input"))
      (node (ref "R4") (pin "2") (pinfunction "2_2") (pintype "input"))
      (node (ref "R5") (pin "2") (pinfunction "2_2") (pintype "input"))
      (node (ref "U10") (pin "1") (pinfunction "1_1") (pintype "unspecified"))
      (node (ref "U10") (pin "3") (pinfunction "3_3") (pintype "unspecified"))
      (node (ref "U10") (pin "5") (pinfunction "5_5") (pintype "unspecified"))
      (node (ref "U10") (pin "7") (pinfunction "7_7") (pintype "unspecified"))
      (node (ref "U15") (pin "1") (pinfunction "1_1") (pintype "unspecified"))
      (node (ref "U15") (pin "2") (pinfunction "2_2") (pintype "unspecified"))
      (node (ref "U21") (pin "4") (pinfunction "TAB_4") (pintype "unspecified"))
      (node (ref "U3") (pin "2") (pinfunction "3V3_2") (pintype "unspecified"))
    )
    (net (code "6") (name "D+") (class "Default")
      (node (ref "D7") (pin "3") (pinfunction "3_3") (pintype "input"))
      (node (ref "U17") (pin "4") (pinfunction "D+_4") (pintype "unspecified"))
      (node (ref "USB1") (pin "6") (pinfunction "DP1_6") (pintype "unspecified"))
      (node (ref "USB1") (pin "8") (pinfunction "DP2_8") (pintype "unspecified"))
    )
    (net (code "7") (name "D-") (class "Default")
      (node (ref "D7") (pin "2") (pinfunction "2_2") (pintype "input"))
      (node (ref "U17") (pin "5") (pinfunction "D-_5") (pintype "unspecified"))
      (node (ref "USB1") (pin "5") (pinfunction "DN2_5") (pintype "unspecified"))
      (node (ref "USB1") (pin "7") (pinfunction "DN1_7") (pintype "unspecified"))
    )
    (net (code "8") (name "ENABLE") (class "Default")
      (node (ref "C3") (pin "2") (pinfunction "2_2") (pintype "unspecified"))
      (node (ref "R12") (pin "1") (pinfunction "1_1") (pintype "unspecified"))
      (node (ref "R28") (pin "2") (pinfunction "2_2") (pintype "input"))
      (node (ref "RESET") (pin "2") (pinfunction "2_2") (pintype "unspecified"))
      (node (ref "U18") (pin "2") (pinfunction "2_2") (pintype "unspecified"))
      (node (ref "U3") (pin "3") (pinfunction "EN_3") (pintype "unspecified"))
    )
    (net (code "9") (name "GND") (class "Default")
      (node (ref "BOOT") (pin "1") (pinfunction "1_1") (pintype "unspecified"))
      (node (ref "C1") (pin "1") (pinfunction "1_1") (pintype "input"))
      (node (ref "C10") (pin "1") (pinfunction "1_1") (pintype "unspecified"))
      (node (ref "C11") (pin "1") (pinfunction "1_1") (pintype "unspecified"))
      (node (ref "C12") (pin "2") (pinfunction "2_2") (pintype "input"))
      (node (ref "C2") (pin "1") (pinfunction "1_1") (pintype "unspecified"))
      (node (ref "C3") (pin "1") (pinfunction "1_1") (pintype "unspecified"))
      (node (ref "C4") (pin "1") (pinfunction "1_1") (pintype "unspecified"))
      (node (ref "C5") (pin "2") (pinfunction "2_2") (pintype "unspecified"))
      (node (ref "C6") (pin "1") (pinfunction "1_1") (pintype "unspecified"))
      (node (ref "C7") (pin "1") (pinfunction "1_1") (pintype "unspecified"))
      (node (ref "C8") (pin "1") (pinfunction "1_1") (pintype "unspecified"))
      (node (ref "C9") (pin "2") (pinfunction "2_2") (pintype "input"))
      (node (ref "D7") (pin "1") (pinfunction "1_1") (pintype "input"))
      (node (ref "LED1") (pin "2") (pinfunction "K_2") (pintype "unspecified"))
      (node (ref "LED2") (pin "1") (pinfunction "-_1") (pintype "unspecified"))
      (node (ref "Q1") (pin "2") (pinfunction "E_2") (pintype "input"))
      (node (ref "Q2") (pin "2") (pinfunction "E_2") (pintype "input"))
      (node (ref "Q3") (pin "2") (pinfunction "E_2") (pintype "input"))
      (node (ref "Q4") (pin "2") (pinfunction "E_2") (pintype "input"))
      (node (ref "Q5") (pin "2") (pinfunction "E_2") (pintype "input"))
      (node (ref "Q6") (pin "2") (pinfunction "E_2") (pintype "input"))
      (node (ref "Q7") (pin "2") (pinfunction "E_2") (pintype "input"))
      (node (ref "Q8") (pin "2") (pinfunction "E_2") (pintype "input"))
      (node (ref "R10") (pin "1") (pinfunction "1_1") (pintype "unspecified"))
      (node (ref "R11") (pin "1") (pinfunction "1_1") (pintype "unspecified"))
      (node (ref "R23") (pin "1") (pinfunction "1_1") (pintype "unspecified"))
      (node (ref "R24") (pin "1") (pinfunction "1_1") (pintype "unspecified"))
      (node (ref "R32") (pin "1") (pinfunction "1_1") (pintype "unspecified"))
      (node (ref "R33") (pin "1") (pinfunction "1_1") (pintype "unspecified"))
      (node (ref "RESET") (pin "1") (pinfunction "1_1") (pintype "unspecified"))
      (node (ref "RGB") (pin "3") (pinfunction "GND_3") (pintype "unspecified"))
      (node (ref "U10") (pin "2") (pinfunction "2_2") (pintype "unspecified"))
      (node (ref "U10") (pin "4") (pinfunction "4_4") (pintype "unspecified"))
      (node (ref "U10") (pin "6") (pinfunction "6_6") (pintype "unspecified"))
      (node (ref "U10") (pin "8") (pinfunction "8_8") (pintype "unspecified"))
      (node (ref "U11") (pin "2") (pinfunction "2_2") (pintype "unspecified"))
      (node (ref "U11") (pin "4") (pinfunction "4_4") (pintype "unspecified"))
      (node (ref "U11") (pin "6") (pinfunction "6_6") (pintype "unspecified"))
      (node (ref "U11") (pin "8") (pinfunction "8_8") (pintype "unspecified"))
      (node (ref "U15") (pin "3") (pinfunction "3_3") (pintype "unspecified"))
      (node (ref "U15") (pin "4") (pinfunction "4_4") (pintype "unspecified"))
      (node (ref "U16") (pin "3") (pinfunction "3_3") (pintype "unspecified"))
      (node (ref "U16") (pin "4") (pinfunction "4_4") (pintype "unspecified"))
      (node (ref "U17") (pin "3") (pinfunction "GND_3") (pintype "unspecified"))
      (node (ref "U18") (pin "1") (pinfunction "1_1") (pintype "unspecified"))
      (node (ref "U20") (pin "3") (pinfunction "-VO_3") (pintype "unspecified"))
      (node (ref "U21") (pin "1") (pinfunction "ADJ(GND)_1") (pintype "unspecified"))
      (node (ref "U22") (pin "2") (pinfunction "GND_2") (pintype "unspecified"))
      (node (ref "U22") (pin "3") (pinfunction "CTL_3") (pintype "unspecified"))
      (node (ref "U3") (pin "1") (pinfunction "GND_1") (pintype "unspecified"))
      (node (ref "U3") (pin "40") (pinfunction "GND_40") (pintype "unspecified"))
      (node (ref "U3") (pin "41") (pinfunction "GND_41") (pintype "unspecified"))
      (node (ref "USB1") (pin "1") (pinfunction "GND_1") (pintype "unspecified"))
      (node (ref "USB1") (pin "12") (pinfunction "GND_12") (pintype "unspecified"))
    )
    (net (code "10") (name "GPIO0") (class "Default")
      (node (ref "BOOT") (pin "2") (pinfunction "2_2") (pintype "unspecified"))
      (node (ref "C5") (pin "1") (pinfunction "1_1") (pintype "unspecified"))
      (node (ref "R13") (pin "1") (pinfunction "1_1") (pintype "unspecified"))
      (node (ref "R31") (pin "2") (pinfunction "2_2") (pintype "input"))
      (node (ref "U3") (pin "27") (pinfunction "IO0_27") (pintype "unspecified"))
    )
    (net (code "11") (name "GPIO1") (class "Default")
      (node (ref "U13") (pin "1") (pinfunction "1_1") (pintype "unspecified"))
      (node (ref "U3") (pin "39") (pinfunction "IO1_39") (pintype "unspecified"))
    )
    (net (code "12") (name "GPIO2") (class "Default")
      (node (ref "U13") (pin "2") (pinfunction "2_2") (pintype "unspecified"))
      (node (ref "U3") (pin "38") (pinfunction "IO2_38") (pintype "unspecified"))
    )
    (net (code "13") (name "GPIO3") (class "Default")
      (node (ref "U14") (pin "1") (pinfunction "1_1") (pintype "unspecified"))
      (node (ref "U3") (pin "15") (pinfunction "IO3_15") (pintype "unspecified"))
    )
    (net (code "14") (name "GPIO4") (class "Default")
      (node (ref "R8") (pin "2") (pinfunction "2_2") (pintype "input"))
      (node (ref "U3") (pin "4") (pinfunction "IO4_4") (pintype "unspecified"))
    )
    (net (code "15") (name "GPIO5") (class "Default")
      (node (ref "R21") (pin "2") (pinfunction "2_2") (pintype "input"))
      (node (ref "U3") (pin "5") (pinfunction "IO5_5") (pintype "unspecified"))
    )
    (net (code "16") (name "GPIO6") (class "Default")
      (node (ref "R9") (pin "2") (pinfunction "2_2") (pintype "input"))
      (node (ref "U3") (pin "6") (pinfunction "IO6_6") (pintype "unspecified"))
    )
    (net (code "17") (name "GPIO7") (class "Default")
      (node (ref "R22") (pin "2") (pinfunction "2_2") (pintype "input"))
      (node (ref "U3") (pin "7") (pinfunction "IO7_7") (pintype "unspecified"))
    )
    (net (code "18") (name "GPIO8") (class "Default")
      (node (ref "U12") (pin "5") (pinfunction "5_5") (pintype "unspecified"))
      (node (ref "U3") (pin "12") (pinfunction "IO8_12") (pintype "unspecified"))
    )
    (net (code "19") (name "GPIO9") (class "Default")
      (node (ref "U14") (pin "3") (pinfunction "3_3") (pintype "unspecified"))
      (node (ref "U3") (pin "17") (pinfunction "IO9_17") (pintype "unspecified"))
    )
    (net (code "20") (name "GPIO10") (class "Default")
      (node (ref "U14") (pin "4") (pinfunction "4_4") (pintype "unspecified"))
      (node (ref "U3") (pin "18") (pinfunction "IO10_18") (pintype "unspecified"))
    )
    (net (code "21") (name "GPIO11") (class "Default")
      (node (ref "U14") (pin "5") (pinfunction "5_5") (pintype "unspecified"))
      (node (ref "U3") (pin "19") (pinfunction "IO11_19") (pintype "unspecified"))
    )
    (net (code "22") (name "GPIO12") (class "Default")
      (node (ref "U14") (pin "6") (pinfunction "6_6") (pintype "unspecified"))
      (node (ref "U3") (pin "20") (pinfunction "IO12_20") (pintype "unspecified"))
    )
    (net (code "23") (name "GPIO13") (class "Default")
      (node (ref "U14") (pin "7") (pinfunction "7_7") (pintype "unspecified"))
      (node (ref "U3") (pin "21") (pinfunction "IO13_21") (pintype "unspecified"))
    )
    (net (code "24") (name "GPIO14") (class "Default")
      (node (ref "U14") (pin "8") (pinfunction "8_8") (pintype "unspecified"))
      (node (ref "U3") (pin "22") (pinfunction "IO14_22") (pintype "unspecified"))
    )
    (net (code "25") (name "GPIO15") (class "Default")
      (node (ref "U12") (pin "1") (pinfunction "1_1") (pintype "unspecified"))
      (node (ref "U3") (pin "8") (pinfunction "IO15_8") (pintype "unspecified"))
    )
    (net (code "26") (name "GPIO16") (class "Default")
      (node (ref "U12") (pin "2") (pinfunction "2_2") (pintype "unspecified"))
      (node (ref "U3") (pin "9") (pinfunction "IO16_9") (pintype "unspecified"))
    )
    (net (code "27") (name "GPIO17") (class "Default")
      (node (ref "U12") (pin "3") (pinfunction "3_3") (pintype "unspecified"))
      (node (ref "U3") (pin "10") (pinfunction "IO17_10") (pintype "unspecified"))
    )
    (net (code "28") (name "GPIO18") (class "Default")
      (node (ref "U12") (pin "4") (pinfunction "4_4") (pintype "unspecified"))
      (node (ref "U3") (pin "11") (pinfunction "IO18_11") (pintype "unspecified"))
    )
    (net (code "29") (name "GPIO19") (class "Default")
      (node (ref "U12") (pin "6") (pinfunction "6_6") (pintype "unspecified"))
      (node (ref "U3") (pin "13") (pinfunction "IO19/USB_D-_13") (pintype "unspecified"))
    )
    (net (code "30") (name "GPIO20") (class "Default")
      (node (ref "U12") (pin "7") (pinfunction "7_7") (pintype "unspecified"))
      (node (ref "U3") (pin "14") (pinfunction "IO20/USB_D+_14") (pintype "unspecified"))
    )
    (net (code "31") (name "GPIO21") (class "Default")
      (node (ref "U14") (pin "9") (pinfunction "9_9") (pintype "unspecified"))
      (node (ref "U3") (pin "23") (pinfunction "IO21_23") (pintype "unspecified"))
    )
    (net (code "32") (name "GPIO35") (class "Default")
      (node (ref "RGB") (pin "4") (pinfunction "DIN_4") (pintype "unspecified"))
      (node (ref "U13") (pin "10") (pinfunction "10_10") (pintype "unspecified"))
      (node (ref "U3") (pin "28") (pinfunction "IO35_28") (pintype "unspecified"))
    )
    (net (code "33") (name "GPIO36") (class "Default")
      (node (ref "U13") (pin "9") (pinfunction "9_9") (pintype "unspecified"))
      (node (ref "U3") (pin "29") (pinfunction "IO36_29") (pintype "unspecified"))
    )
    (net (code "34") (name "GPIO37") (class "Default")
      (node (ref "U13") (pin "8") (pinfunction "8_8") (pintype "unspecified"))
      (node (ref "U3") (pin "30") (pinfunction "IO37_30") (pintype "unspecified"))
    )
    (net (code "35") (name "GPIO38") (class "Default")
      (node (ref "U13") (pin "7") (pinfunction "7_7") (pintype "unspecified"))
      (node (ref "U3") (pin "31") (pinfunction "IO38_31") (pintype "unspecified"))
    )
    (net (code "36") (name "GPIO39") (class "Default")
      (node (ref "U13") (pin "6") (pinfunction "6_6") (pintype "unspecified"))
      (node (ref "U3") (pin "32") (pinfunction "IO39_32") (pintype "unspecified"))
    )
    (net (code "37") (name "GPIO40") (class "Default")
      (node (ref "U13") (pin "5") (pinfunction "5_5") (pintype "unspecified"))
      (node (ref "U3") (pin "33") (pinfunction "IO40_33") (pintype "unspecified"))
    )
    (net (code "38") (name "GPIO41") (class "Default")
      (node (ref "U13") (pin "4") (pinfunction "4_4") (pintype "unspecified"))
      (node (ref "U3") (pin "34") (pinfunction "IO41_34") (pintype "unspecified"))
    )
    (net (code "39") (name "GPIO42") (class "Default")
      (node (ref "U13") (pin "3") (pinfunction "3_3") (pintype "unspecified"))
      (node (ref "U3") (pin "35") (pinfunction "IO42_35") (pintype "unspecified"))
    )
    (net (code "40") (name "GPIO45") (class "Default")
      (node (ref "U14") (pin "12") (pinfunction "12_12") (pintype "unspecified"))
      (node (ref "U3") (pin "26") (pinfunction "IO45_26") (pintype "unspecified"))
    )
    (net (code "41") (name "GPIO46") (class "Default")
      (node (ref "U14") (pin "2") (pinfunction "2_2") (pintype "unspecified"))
      (node (ref "U3") (pin "16") (pinfunction "IO46_16") (pintype "unspecified"))
    )
    (net (code "42") (name "GPIO47") (class "Default")
      (node (ref "U14") (pin "10") (pinfunction "10_10") (pintype "unspecified"))
      (node (ref "U3") (pin "24") (pinfunction "IO47_24") (pintype "unspecified"))
    )
    (net (code "43") (name "GPIO48") (class "Default")
      (node (ref "U14") (pin "11") (pinfunction "11_11") (pintype "unspecified"))
      (node (ref "U3") (pin "25") (pinfunction "IO48_25") (pintype "unspecified"))
    )
    (net (code "44") (name "Net-(D1-A)") (class "Default")
      (node (ref "D1") (pin "2") (pinfunction "A_2") (pintype "unspecified"))
      (node (ref "K1") (pin "1") (pinfunction "1_1") (pintype "unspecified"))
      (node (ref "Q1") (pin "3") (pinfunction "C_3") (pintype "input"))
    )
    (net (code "45") (name "Net-(D2-A)") (class "Default")
      (node (ref "D2") (pin "2") (pinfunction "A_2") (pintype "unspecified"))
      (node (ref "K2") (pin "1") (pinfunction "1_1") (pintype "unspecified"))
      (node (ref "Q2") (pin "3") (pinfunction "C_3") (pintype "input"))
    )
    (net (code "46") (name "Net-(D3-A)") (class "Default")
      (node (ref "D3") (pin "2") (pinfunction "A_2") (pintype "unspecified"))
      (node (ref "K3") (pin "1") (pinfunction "1_1") (pintype "unspecified"))
      (node (ref "Q5") (pin "3") (pinfunction "C_3") (pintype "input"))
    )
    (net (code "47") (name "Net-(D4-A)") (class "Default")
      (node (ref "D4") (pin "2") (pinfunction "A_2") (pintype "unspecified"))
      (node (ref "K4") (pin "1") (pinfunction "1_1") (pintype "unspecified"))
      (node (ref "Q6") (pin "3") (pinfunction "C_3") (pintype "input"))
    )
    (net (code "48") (name "Net-(GREEN-+)") (class "Default")
      (node (ref "GREEN") (pin "1") (pinfunction "+_1") (pintype "unspecified"))
      (node (ref "R4") (pin "1") (pinfunction "1_1") (pintype "input"))
    )
    (net (code "49") (name "Net-(GREEN--)") (class "Default")
      (node (ref "GREEN") (pin "2") (pinfunction "-_2") (pintype "unspecified"))
      (node (ref "Q3") (pin "3") (pinfunction "C_3") (pintype "input"))
      (node (ref "U4") (pin "2") (pinfunction "CAT_2") (pintype "unspecified"))
    )
    (net (code "50") (name "Net-(GREEN1-+)") (class "Default")
      (node (ref "GREEN1") (pin "1") (pinfunction "+_1") (pintype "unspecified"))
      (node (ref "R5") (pin "1") (pinfunction "1_1") (pintype "input"))
    )
    (net (code "51") (name "Net-(GREEN1--)") (class "Default")
      (node (ref "GREEN1") (pin "2") (pinfunction "-_2") (pintype "unspecified"))
      (node (ref "Q4") (pin "3") (pinfunction "C_3") (pintype "input"))
      (node (ref "U5") (pin "2") (pinfunction "CAT_2") (pintype "unspecified"))
    )
    (net (code "52") (name "Net-(GREEN2-+)") (class "Default")
      (node (ref "GREEN2") (pin "1") (pinfunction "+_1") (pintype "unspecified"))
      (node (ref "R16") (pin "1") (pinfunction "1_1") (pintype "input"))
    )
    (net (code "53") (name "Net-(GREEN2--)") (class "Default")
      (node (ref "GREEN2") (pin "2") (pinfunction "-_2") (pintype "unspecified"))
      (node (ref "Q7") (pin "3") (pinfunction "C_3") (pintype "input"))
      (node (ref "U8") (pin "2") (pinfunction "CAT_2") (pintype "unspecified"))
    )
    (net (code "54") (name "Net-(GREEN3-+)") (class "Default")
      (node (ref "GREEN3") (pin "1") (pinfunction "+_1") (pintype "unspecified"))
      (node (ref "R17") (pin "1") (pinfunction "1_1") (pintype "input"))
    )
    (net (code "55") (name "Net-(GREEN3--)") (class "Default")
      (node (ref "GREEN3") (pin "2") (pinfunction "-_2") (pintype "unspecified"))
      (node (ref "Q8") (pin "3") (pinfunction "C_3") (pintype "input"))
      (node (ref "U9") (pin "2") (pinfunction "CAT_2") (pintype "unspecified"))
    )
    (net (code "56") (name "Net-(K1-COM)") (class "Default")
      (node (ref "K1") (pin "2") (pinfunction "COM_2") (pintype "unspecified"))
      (node (ref "U1") (pin "2") (pinfunction "2_2") (pintype "unspecified"))
    )
    (net (code "57") (name "Net-(K1-N.C.)") (class "Default")
      (node (ref "K1") (pin "4") (pinfunction "N.C._4") (pintype "unspecified"))
      (node (ref "U1") (pin "1") (pinfunction "1_1") (pintype "unspecified"))
    )
    (net (code "58") (name "Net-(K1-N.O.)") (class "Default")
      (node (ref "K1") (pin "3") (pinfunction "N.O._3") (pintype "unspecified"))
      (node (ref "U1") (pin "3") (pinfunction "3_3") (pintype "unspecified"))
    )
    (net (code "59") (name "Net-(K2-COM)") (class "Default")
      (node (ref "K2") (pin "2") (pinfunction "COM_2") (pintype "unspecified"))
      (node (ref "U2") (pin "2") (pinfunction "2_2") (pintype "unspecified"))
    )
    (net (code "60") (name "Net-(K2-N.C.)") (class "Default")
      (node (ref "K2") (pin "4") (pinfunction "N.C._4") (pintype "unspecified"))
      (node (ref "U2") (pin "1") (pinfunction "1_1") (pintype "unspecified"))
    )
    (net (code "61") (name "Net-(K2-N.O.)") (class "Default")
      (node (ref "K2") (pin "3") (pinfunction "N.O._3") (pintype "unspecified"))
      (node (ref "U2") (pin "3") (pinfunction "3_3") (pintype "unspecified"))
    )
    (net (code "62") (name "Net-(K3-COM)") (class "Default")
      (node (ref "K3") (pin "2") (pinfunction "COM_2") (pintype "unspecified"))
      (node (ref "U6") (pin "2") (pinfunction "2_2") (pintype "unspecified"))
    )
    (net (code "63") (name "Net-(K3-N.C.)") (class "Default")
      (node (ref "K3") (pin "4") (pinfunction "N.C._4") (pintype "unspecified"))
      (node (ref "U6") (pin "1") (pinfunction "1_1") (pintype "unspecified"))
    )
    (net (code "64") (name "Net-(K3-N.O.)") (class "Default")
      (node (ref "K3") (pin "3") (pinfunction "N.O._3") (pintype "unspecified"))
      (node (ref "U6") (pin "3") (pinfunction "3_3") (pintype "unspecified"))
    )
    (net (code "65") (name "Net-(K4-COM)") (class "Default")
      (node (ref "K4") (pin "2") (pinfunction "COM_2") (pintype "unspecified"))
      (node (ref "U7") (pin "2") (pinfunction "2_2") (pintype "unspecified"))
    )
    (net (code "66") (name "Net-(K4-N.C.)") (class "Default")
      (node (ref "K4") (pin "4") (pinfunction "N.C._4") (pintype "unspecified"))
      (node (ref "U7") (pin "1") (pinfunction "1_1") (pintype "unspecified"))
    )
    (net (code "67") (name "Net-(K4-N.O.)") (class "Default")
      (node (ref "K4") (pin "3") (pinfunction "N.O._3") (pintype "unspecified"))
      (node (ref "U7") (pin "3") (pinfunction "3_3") (pintype "unspecified"))
    )
    (net (code "68") (name "Net-(LED1-A)") (class "Default")
      (node (ref "LED1") (pin "1") (pinfunction "A_1") (pintype "unspecified"))
      (node (ref "R20") (pin "2") (pinfunction "2_2") (pintype "unspecified"))
    )
    (net (code "69") (name "Net-(LED2-+)") (class "Default")
      (node (ref "LED2") (pin "2") (pinfunction "+_2") (pintype "unspecified"))
      (node (ref "R25") (pin "2") (pinfunction "2_2") (pintype "unspecified"))
    )
    (net (code "70") (name "Net-(Q1-B)") (class "Default")
      (node (ref "Q1") (pin "1") (pinfunction "B_1") (pintype "input"))
      (node (ref "R6") (pin "1") (pinfunction "1_1") (pintype "input"))
    )
    (net (code "71") (name "Net-(Q2-B)") (class "Default")
      (node (ref "Q2") (pin "1") (pinfunction "B_1") (pintype "input"))
      (node (ref "R7") (pin "1") (pinfunction "1_1") (pintype "input"))
    )
    (net (code "72") (name "Net-(Q3-B)") (class "Default")
      (node (ref "Q3") (pin "1") (pinfunction "B_1") (pintype "input"))
      (node (ref "R10") (pin "2") (pinfunction "2_2") (pintype "unspecified"))
      (node (ref "R8") (pin "1") (pinfunction "1_1") (pintype "input"))
    )
    (net (code "73") (name "Net-(Q4-B)") (class "Default")
      (node (ref "Q4") (pin "1") (pinfunction "B_1") (pintype "input"))
      (node (ref "R11") (pin "2") (pinfunction "2_2") (pintype "unspecified"))
      (node (ref "R9") (pin "1") (pinfunction "1_1") (pintype "input"))
    )
    (net (code "74") (name "Net-(Q5-B)") (class "Default")
      (node (ref "Q5") (pin "1") (pinfunction "B_1") (pintype "input"))
      (node (ref "R18") (pin "1") (pinfunction "1_1") (pintype "input"))
    )
    (net (code "75") (name "Net-(Q6-B)") (class "Default")
      (node (ref "Q6") (pin "1") (pinfunction "B_1") (pintype "input"))
      (node (ref "R19") (pin "1") (pinfunction "1_1") (pintype "input"))
    )
    (net (code "76") (name "Net-(Q7-B)") (class "Default")
      (node (ref "Q7") (pin "1") (pinfunction "B_1") (pintype "input"))
      (node (ref "R21") (pin "1") (pinfunction "1_1") (pintype "input"))
      (node (ref "R23") (pin "2") (pinfunction "2_2") (pintype "unspecified"))
    )
    (net (code "77") (name "Net-(Q8-B)") (class "Default")
      (node (ref "Q8") (pin "1") (pinfunction "B_1") (pintype "input"))
      (node (ref "R22") (pin "1") (pinfunction "1_1") (pintype "input"))
      (node (ref "R24") (pin "2") (pinfunction "2_2") (pintype "unspecified"))
    )
    (net (code "78") (name "Net-(Q9-B)") (class "Default")
      (node (ref "Q9") (pin "1") (pinfunction "B_1") (pintype "unspecified"))
      (node (ref "R29") (pin "2") (pinfunction "2_2") (pintype "unspecified"))
    )
    (net (code "79") (name "Net-(Q9-C)") (class "Default")
      (node (ref "Q9") (pin "3") (pinfunction "C_3") (pintype "unspecified"))
      (node (ref "R28") (pin "1") (pinfunction "1_1") (pintype "input"))
    )
    (net (code "80") (name "Net-(Q10-D)") (class "Default")
      (node (ref "F1") (pin "2") (pinfunction "2_2") (pintype "unspecified"))
      (node (ref "Q10") (pin "3") (pinfunction "D_3") (pintype "unspecified"))
      (node (ref "U22") (pin "1") (pinfunction "VIN_1") (pintype "unspecified"))
    )
    (net (code "81") (name "Net-(Q10-G)") (class "Default")
      (node (ref "Q10") (pin "1") (pinfunction "G_1") (pintype "unspecified"))
      (node (ref "U22") (pin "5") (pinfunction "GATE_5") (pintype "unspecified"))
    )
    (net (code "82") (name "Net-(Q11-B)") (class "Default")
      (node (ref "Q11") (pin "1") (pinfunction "B_1") (pintype "unspecified"))
      (node (ref "R30") (pin "2") (pinfunction "2_2") (pintype "unspecified"))
    )
    (net (code "83") (name "Net-(Q11-C)") (class "Default")
      (node (ref "Q11") (pin "3") (pinfunction "C_3") (pintype "unspecified"))
      (node (ref "R31") (pin "1") (pinfunction "1_1") (pintype "input"))
    )
    (net (code "84") (name "Net-(RX-+)") (class "Default")
      (node (ref "R27") (pin "2") (pinfunction "2_2") (pintype "unspecified"))
      (node (ref "RX") (pin "1") (pinfunction "+_1") (pintype "unspecified"))
    )
    (net (code "85") (name "Net-(TX-A)") (class "Default")
      (node (ref "R26") (pin "2") (pinfunction "2_2") (pintype "unspecified"))
      (node (ref "TX") (pin "2") (pinfunction "A_2") (pintype "unspecified"))
    )
    (net (code "86") (name "Net-(U4-AN)") (class "Default")
      (node (ref "R2") (pin "1") (pinfunction "1_1") (pintype "input"))
      (node (ref "U4") (pin "1") (pinfunction "AN_1") (pintype "unspecified"))
    )
    (net (code "87") (name "Net-(U4-EMI)") (class "Default")
      (node (ref "R6") (pin "2") (pinfunction "2_2") (pintype "input"))
      (node (ref "U4") (pin "3") (pinfunction "EMI_3") (pintype "unspecified"))
    )
    (net (code "88") (name "Net-(U5-AN)") (class "Default")
      (node (ref "R3") (pin "1") (pinfunction "1_1") (pintype "input"))
      (node (ref "U5") (pin "1") (pinfunction "AN_1") (pintype "unspecified"))
    )
    (net (code "89") (name "Net-(U5-EMI)") (class "Default")
      (node (ref "R7") (pin "2") (pinfunction "2_2") (pintype "input"))
      (node (ref "U5") (pin "3") (pinfunction "EMI_3") (pintype "unspecified"))
    )
    (net (code "90") (name "Net-(U8-AN)") (class "Default")
      (node (ref "R14") (pin "1") (pinfunction "1_1") (pintype "input"))
      (node (ref "U8") (pin "1") (pinfunction "AN_1") (pintype "unspecified"))
    )
    (net (code "91") (name "Net-(U8-EMI)") (class "Default")
      (node (ref "R18") (pin "2") (pinfunction "2_2") (pintype "input"))
      (node (ref "U8") (pin "3") (pinfunction "EMI_3") (pintype "unspecified"))
    )
    (net (code "92") (name "Net-(U9-AN)") (class "Default")
      (node (ref "R15") (pin "1") (pinfunction "1_1") (pintype "input"))
      (node (ref "U9") (pin "1") (pinfunction "AN_1") (pintype "unspecified"))
    )
    (net (code "93") (name "Net-(U9-EMI)") (class "Default")
      (node (ref "R19") (pin "2") (pinfunction "2_2") (pintype "input"))
      (node (ref "U9") (pin "3") (pinfunction "EMI_3") (pintype "unspecified"))
    )
    (net (code "94") (name "Net-(U17-VDD)") (class "Default")
      (node (ref "C4") (pin "2") (pinfunction "2_2") (pintype "unspecified"))
      (node (ref "U17") (pin "6") (pinfunction "VDD_6") (pintype "unspecified"))
    )
    (net (code "95") (name "Net-(U19-Pad1)") (class "Default")
      (node (ref "U19") (pin "1") (pinfunction "1_1") (pintype "unspecified"))
      (node (ref "U20") (pin "2") (pinfunction "AC_2") (pintype "unspecified"))
    )
    (net (code "96") (name "Net-(U19-Pad2)") (class "Default")
      (node (ref "U19") (pin "2") (pinfunction "2_2") (pintype "unspecified"))
      (node (ref "U20") (pin "1") (pinfunction "AC_1") (pintype "unspecified"))
    )
    (net (code "97") (name "Net-(U20-+VO)") (class "Default")
      (node (ref "F1") (pin "1") (pinfunction "1_1") (pintype "unspecified"))
      (node (ref "U20") (pin "4") (pinfunction "+VO_4") (pintype "unspecified"))
    )
    (net (code "98") (name "UORXD") (class "Default")
      (node (ref "RX") (pin "2") (pinfunction "-_2") (pintype "unspecified"))
      (node (ref "U17") (pin "26") (pinfunction "TXD_26") (pintype "unspecified"))
      (node (ref "U3") (pin "36") (pinfunction "RXD0_36") (pintype "unspecified"))
    )
    (net (code "99") (name "UOTXD") (class "Default")
      (node (ref "TX") (pin "1") (pinfunction "K_1") (pintype "unspecified"))
      (node (ref "U17") (pin "25") (pinfunction "RXD_25") (pintype "unspecified"))
      (node (ref "U3") (pin "37") (pinfunction "TXD0_37") (pintype "unspecified"))
    )
    (net (code "100") (name "USB_DTR") (class "Default")
      (node (ref "Q11") (pin "2") (pinfunction "E_2") (pintype "unspecified"))
      (node (ref "R29") (pin "1") (pinfunction "1_1") (pintype "unspecified"))
      (node (ref "U17") (pin "28") (pinfunction "DTR_28") (pintype "unspecified"))
    )
    (net (code "101") (name "USB_RTS") (class "Default")
      (node (ref "Q9") (pin "2") (pinfunction "E_2") (pintype "unspecified"))
      (node (ref "R30") (pin "1") (pinfunction "1_1") (pintype "unspecified"))
      (node (ref "U17") (pin "24") (pinfunction "RTS_24") (pintype "unspecified"))
    )
    (net (code "102") (name "VDDUSB") (class "Default")
      (node (ref "C6") (pin "2") (pinfunction "2_2") (pintype "unspecified"))
      (node (ref "C7") (pin "2") (pinfunction "2_2") (pintype "unspecified"))
      (node (ref "C8") (pin "2") (pinfunction "2_2") (pintype "unspecified"))
      (node (ref "D5") (pin "2") (pinfunction "A_2") (pintype "unspecified"))
      (node (ref "D6") (pin "1") (pinfunction "K_1") (pintype "unspecified"))
      (node (ref "U17") (pin "7") (pinfunction "REGIN_7") (pintype "unspecified"))
      (node (ref "U17") (pin "8") (pinfunction "VBUS_8") (pintype "unspecified"))
    )
    (net (code "103") (name "unconnected-(RGB-DOU-Pad2)") (class "Default")
      (node (ref "RGB") (pin "2") (pinfunction "DOU_2") (pintype "unspecified+no_connect"))
    )
    (net (code "104") (name "unconnected-(U17-CTS-Pad23)") (class "Default")
      (node (ref "U17") (pin "23") (pinfunction "CTS_23") (pintype "unspecified+no_connect"))
    )
    (net (code "105") (name "unconnected-(U17-DCD-Pad1)") (class "Default")
      (node (ref "U17") (pin "1") (pinfunction "DCD_1") (pintype "unspecified+no_connect"))
    )
    (net (code "106") (name "unconnected-(U17-DSR-Pad27)") (class "Default")
      (node (ref "U17") (pin "27") (pinfunction "DSR_27") (pintype "unspecified+no_connect"))
    )
    (net (code "107") (name "unconnected-(U17-EP-Pad29)") (class "Default")
      (node (ref "U17") (pin "29") (pinfunction "EP_29") (pintype "unspecified+no_connect"))
    )
    (net (code "108") (name "unconnected-(U17-NC-Pad10)") (class "Default")
      (node (ref "U17") (pin "10") (pinfunction "NC_10") (pintype "unspecified+no_connect"))
    )
    (net (code "109") (name "unconnected-(U17-NC-Pad13)") (class "Default")
      (node (ref "U17") (pin "13") (pinfunction "NC_13") (pintype "unspecified+no_connect"))
    )
    (net (code "110") (name "unconnected-(U17-NC-Pad14)") (class "Default")
      (node (ref "U17") (pin "14") (pinfunction "NC_14") (pintype "unspecified+no_connect"))
    )
    (net (code "111") (name "unconnected-(U17-NC-Pad15)") (class "Default")
      (node (ref "U17") (pin "15") (pinfunction "NC_15") (pintype "unspecified+no_connect"))
    )
    (net (code "112") (name "unconnected-(U17-NC-Pad16)") (class "Default")
      (node (ref "U17") (pin "16") (pinfunction "NC_16") (pintype "unspecified+no_connect"))
    )
    (net (code "113") (name "unconnected-(U17-NC-Pad17)") (class "Default")
      (node (ref "U17") (pin "17") (pinfunction "NC_17") (pintype "unspecified+no_connect"))
    )
    (net (code "114") (name "unconnected-(U17-NC-Pad18)") (class "Default")
      (node (ref "U17") (pin "18") (pinfunction "NC_18") (pintype "unspecified+no_connect"))
    )
    (net (code "115") (name "unconnected-(U17-NC-Pad19)") (class "Default")
      (node (ref "U17") (pin "19") (pinfunction "NC_19") (pintype "unspecified+no_connect"))
    )
    (net (code "116") (name "unconnected-(U17-NC-Pad20)") (class "Default")
      (node (ref "U17") (pin "20") (pinfunction "NC_20") (pintype "unspecified+no_connect"))
    )
    (net (code "117") (name "unconnected-(U17-NC-Pad21)") (class "Default")
      (node (ref "U17") (pin "21") (pinfunction "NC_21") (pintype "unspecified+no_connect"))
    )
    (net (code "118") (name "unconnected-(U17-NC-Pad22)") (class "Default")
      (node (ref "U17") (pin "22") (pinfunction "NC_22") (pintype "unspecified+no_connect"))
    )
    (net (code "119") (name "unconnected-(U17-RI-Pad2)") (class "Default")
      (node (ref "U17") (pin "2") (pinfunction "RI_2") (pintype "unspecified+no_connect"))
    )
    (net (code "120") (name "unconnected-(U17-RST#-Pad9)") (class "Default")
      (node (ref "U17") (pin "9") (pinfunction "RST#_9") (pintype "unspecified+no_connect"))
    )
    (net (code "121") (name "unconnected-(U17-SUSPEND#-Pad11)") (class "Default")
      (node (ref "U17") (pin "11") (pinfunction "SUSPEND#_11") (pintype "unspecified+no_connect"))
    )
    (net (code "122") (name "unconnected-(U17-SUSPEND-Pad12)") (class "Default")
      (node (ref "U17") (pin "12") (pinfunction "SUSPEND_12") (pintype "unspecified+no_connect"))
    )
    (net (code "123") (name "unconnected-(U21-VOUT(TAB)-Pad2)") (class "Default")
      (node (ref "U21") (pin "2") (pinfunction "VOUT(TAB)_2") (pintype "unspecified+no_connect"))
    )
    (net (code "124") (name "unconnected-(U22-STAT-Pad4)") (class "Default")
      (node (ref "U22") (pin "4") (pinfunction "STAT_4") (pintype "unspecified+no_connect"))
    )
    (net (code "125") (name "unconnected-(USB1-SBU1-Pad9)") (class "Default")
      (node (ref "USB1") (pin "9") (pinfunction "SBU1_9") (pintype "unspecified+no_connect"))
    )
    (net (code "126") (name "unconnected-(USB1-SBU2-Pad3)") (class "Default")
      (node (ref "USB1") (pin "3") (pinfunction "SBU2_3") (pintype "unspecified+no_connect"))
    )
    (net (code "127") (name "unconnected-(USB1-SHELL-Pad13)") (class "Default")
      (node (ref "USB1") (pin "13") (pinfunction "SHELL_13") (pintype "unspecified+no_connect"))
    )
    (net (code "128") (name "unconnected-(USB1-SHELL-Pad14)") (class "Default")
      (node (ref "USB1") (pin "14") (pinfunction "SHELL_14") (pintype "unspecified+no_connect"))
    )
  )
)
